# ST-LINK.net
KiCad netlist of a schematic drawn in Altium Designer
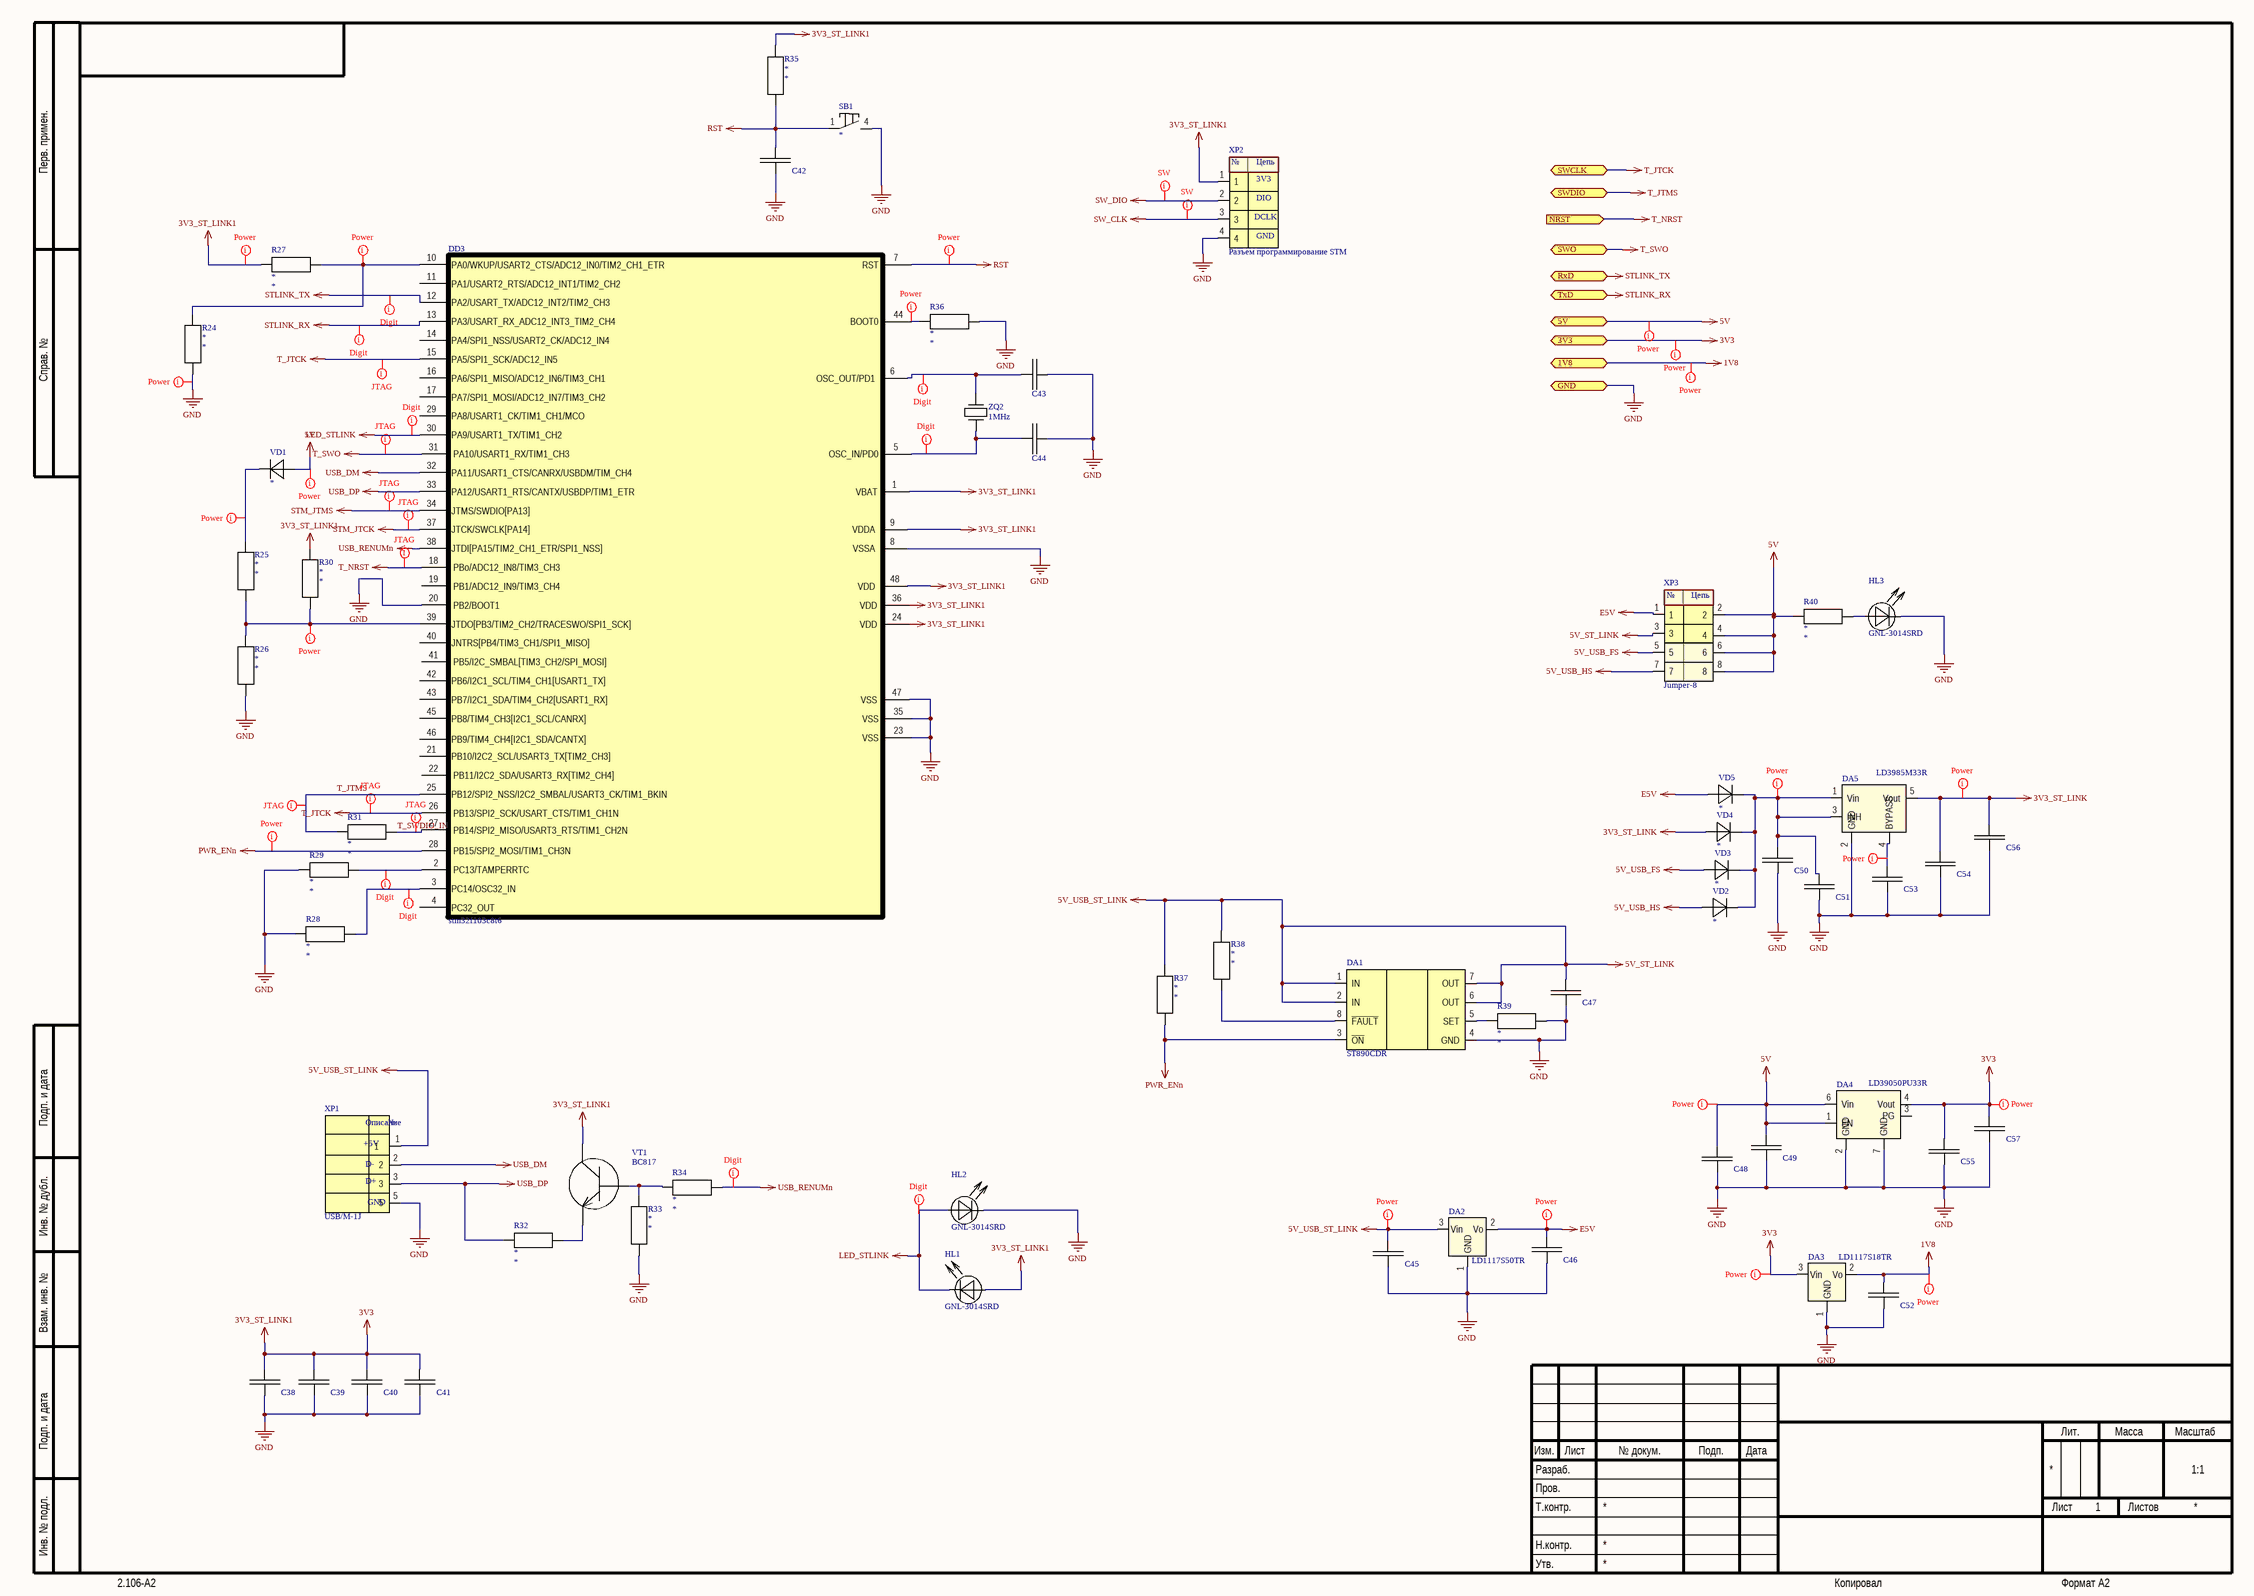
[diagram p0: ST-LINK.SchDoc]

(export (version "E")
  (design (tool "Eeschema 10.0.6"))
  (components
    (comp (ref "C38") (value "*") (footprint "CAP0402") (libsource (lib "SchlibUGO") (part "Capasitor")))
    (comp (ref "C39") (value "*") (footprint "CAP0402") (libsource (lib "SchlibUGO") (part "Capasitor")))
    (comp (ref "C40") (value "*") (footprint "CAP0402") (libsource (lib "SchlibUGO") (part "Capasitor")))
    (comp (ref "C41") (value "*") (footprint "CAP0402") (libsource (lib "SchlibUGO") (part "Capasitor")))
    (comp (ref "C42") (value "*") (footprint "CAP0402") (libsource (lib "SchlibUGO") (part "Capasitor")))
    (comp (ref "C43") (value "*") (footprint "CAP0402") (libsource (lib "SchlibUGO") (part "Capasitor")))
    (comp (ref "C44") (value "*") (footprint "CAP0402") (libsource (lib "SchlibUGO") (part "Capasitor")))
    (comp (ref "C45") (value "*") (footprint "CAP0402") (libsource (lib "SchlibUGO") (part "Capasitor")))
    (comp (ref "C46") (value "*") (footprint "CAP0402") (libsource (lib "SchlibUGO") (part "Capasitor")))
    (comp (ref "C47") (value "*") (footprint "CAP0402") (libsource (lib "SchlibUGO") (part "Capasitor")))
    (comp (ref "C48") (value "*") (footprint "CAP0402") (libsource (lib "SchlibUGO") (part "Capasitor")))
    (comp (ref "C49") (value "*") (footprint "CAP0402") (libsource (lib "SchlibUGO") (part "Capasitor")))
    (comp (ref "C50") (value "*") (footprint "CAP0402") (libsource (lib "SchlibUGO") (part "Capasitor")))
    (comp (ref "C51") (value "*") (footprint "CAP0402") (libsource (lib "SchlibUGO") (part "Capasitor")))
    (comp (ref "C52") (value "*") (footprint "CAP0402") (libsource (lib "SchlibUGO") (part "Capasitor")))
    (comp (ref "C53") (value "*") (footprint "CAP0402") (libsource (lib "SchlibUGO") (part "Capasitor")))
    (comp (ref "C54") (value "*") (footprint "CAP0402") (libsource (lib "SchlibUGO") (part "Capasitor")))
    (comp (ref "C55") (value "*") (footprint "CAP0402") (libsource (lib "SchlibUGO") (part "Capasitor")))
    (comp (ref "C56") (value "*") (footprint "CAP0402") (libsource (lib "SchlibUGO") (part "Capasitor")))
    (comp (ref "C57") (value "*") (footprint "CAP0402") (libsource (lib "SchlibUGO") (part "Capasitor")))
    (comp (ref "DA1")
      (value "ST890CDR")
      (footprint "SO-8")
      (fields (field (name "MANUFACTURER") "Texas Instruments"))
      (libsource (lib "SchlibUGO") (part "ST890CDR"))
    )
    (comp (ref "DA2")
      (value "LD1117S50TR")
      (footprint "SOD-223")
      (fields (field (name "MANUFACTURER") "Texas Instruments"))
      (libsource (lib "SchlibUGO") (part "LD1117S50TR"))
    )
    (comp (ref "DA3")
      (value "LD1117S18TR")
      (footprint "SOD-223")
      (fields (field (name "MANUFACTURER") "Texas Instruments"))
      (libsource (lib "SchlibUGO") (part "LD1117S18TR"))
    )
    (comp (ref "DA4")
      (value "LD39050PU33R")
      (footprint "DFN-6(3x3)")
      (fields (field (name "MANUFACTURER") "Texas Instruments"))
      (libsource (lib "SchlibUGO") (part "LD39050PU33R"))
    )
    (comp (ref "DA5")
      (value "LD3985M33R")
      (footprint "SOT23-5")
      (fields (field (name "MANUFACTURER") "Texas Instruments"))
      (libsource (lib "SchlibUGO") (part "LD3985M33R"))
    )
    (comp (ref "DD3")
      (value "stm32f103c8t6")
      (footprint "LQFP48")
      (fields (field (name "MANUFACTURER") "STM"))
      (libsource (lib "SchlibUGO") (part "stm32f103c8t6"))
    )
    (comp (ref "HL1")
      (value "GNL-3014SRD")
      (footprint "LED1206")
      (fields (field (name "MANUFACTURER") "G-NOR"))
      (libsource (lib "") (part "LED_1"))
    )
    (comp (ref "HL2")
      (value "GNL-3014SRD")
      (footprint "LED1206")
      (fields (field (name "MANUFACTURER") "G-NOR"))
      (libsource (lib "SchlibUGO") (part "LED"))
    )
    (comp (ref "HL3")
      (value "GNL-3014SRD")
      (footprint "LED1206")
      (fields (field (name "MANUFACTURER") "G-NOR"))
      (libsource (lib "SchlibUGO") (part "LED"))
    )
    (comp (ref "R24")
      (value "*")
      (footprint "0402")
      (fields (field (name "ALTIUM_VALUE") "*") (field (name "POWER") "*"))
      (libsource (lib "SchlibUGO") (part "Resistor"))
    )
    (comp (ref "R25")
      (value "*")
      (footprint "0402")
      (fields (field (name "ALTIUM_VALUE") "*") (field (name "POWER") "*"))
      (libsource (lib "SchlibUGO") (part "Resistor"))
    )
    (comp (ref "R26")
      (value "*")
      (footprint "0402")
      (fields (field (name "ALTIUM_VALUE") "*") (field (name "POWER") "*"))
      (libsource (lib "SchlibUGO") (part "Resistor"))
    )
    (comp (ref "R27")
      (value "*")
      (footprint "0402")
      (fields (field (name "ALTIUM_VALUE") "*") (field (name "POWER") "*"))
      (libsource (lib "SchlibUGO") (part "Resistor"))
    )
    (comp (ref "R28")
      (value "*")
      (footprint "0402")
      (fields (field (name "ALTIUM_VALUE") "*") (field (name "POWER") "*"))
      (libsource (lib "SchlibUGO") (part "Resistor"))
    )
    (comp (ref "R29")
      (value "*")
      (footprint "0402")
      (fields (field (name "ALTIUM_VALUE") "*") (field (name "POWER") "*"))
      (libsource (lib "SchlibUGO") (part "Resistor"))
    )
    (comp (ref "R30")
      (value "*")
      (footprint "0402")
      (fields (field (name "ALTIUM_VALUE") "*") (field (name "POWER") "*"))
      (libsource (lib "SchlibUGO") (part "Resistor"))
    )
    (comp (ref "R31")
      (value "*")
      (footprint "0402")
      (fields (field (name "ALTIUM_VALUE") "*") (field (name "POWER") "*"))
      (libsource (lib "SchlibUGO") (part "Resistor"))
    )
    (comp (ref "R32")
      (value "*")
      (footprint "0402")
      (fields (field (name "ALTIUM_VALUE") "*") (field (name "POWER") "*"))
      (libsource (lib "SchlibUGO") (part "Resistor"))
    )
    (comp (ref "R33")
      (value "*")
      (footprint "0402")
      (fields (field (name "ALTIUM_VALUE") "*") (field (name "POWER") "*"))
      (libsource (lib "SchlibUGO") (part "Resistor"))
    )
    (comp (ref "R34")
      (value "*")
      (footprint "0402")
      (fields (field (name "ALTIUM_VALUE") "*") (field (name "POWER") "*"))
      (libsource (lib "SchlibUGO") (part "Resistor"))
    )
    (comp (ref "R35")
      (value "*")
      (footprint "0402")
      (fields (field (name "ALTIUM_VALUE") "*") (field (name "POWER") "*"))
      (libsource (lib "SchlibUGO") (part "Resistor"))
    )
    (comp (ref "R36")
      (value "*")
      (footprint "0402")
      (fields (field (name "ALTIUM_VALUE") "*") (field (name "POWER") "*"))
      (libsource (lib "SchlibUGO") (part "Resistor"))
    )
    (comp (ref "R37")
      (value "*")
      (footprint "0402")
      (fields (field (name "ALTIUM_VALUE") "*") (field (name "POWER") "*"))
      (libsource (lib "SchlibUGO") (part "Resistor"))
    )
    (comp (ref "R38")
      (value "*")
      (footprint "0402")
      (fields (field (name "ALTIUM_VALUE") "*") (field (name "POWER") "*"))
      (libsource (lib "SchlibUGO") (part "Resistor"))
    )
    (comp (ref "R39")
      (value "*")
      (footprint "0402")
      (fields (field (name "ALTIUM_VALUE") "*") (field (name "POWER") "*"))
      (libsource (lib "SchlibUGO") (part "Resistor"))
    )
    (comp (ref "R40")
      (value "*")
      (footprint "0402")
      (fields (field (name "ALTIUM_VALUE") "*") (field (name "POWER") "*"))
      (libsource (lib "SchlibUGO") (part "Resistor"))
    )
    (comp (ref "SB1") (value "*") (footprint "KLS2") (libsource (lib "SchlibUGO") (part "Button")))
    (comp (ref "VD1") (value "*") (footprint "melf") (libsource (lib "Diode_Library") (part "Basic_Diode")))
    (comp (ref "VD2")
      (value "*")
      (footprint "MINIMELF")
      (libsource (lib "Diode_Library") (part "Basic_Diode"))
    )
    (comp (ref "VD3")
      (value "*")
      (footprint "MINIMELF")
      (libsource (lib "Diode_Library") (part "Basic_Diode"))
    )
    (comp (ref "VD4")
      (value "*")
      (footprint "MINIMELF")
      (libsource (lib "Diode_Library") (part "Basic_Diode"))
    )
    (comp (ref "VD5")
      (value "*")
      (footprint "MINIMELF")
      (libsource (lib "Diode_Library") (part "Basic_Diode"))
    )
    (comp (ref "VT1")
      (value "BC817")
      (footprint "SOT23-3")
      (fields (field (name "MANUFACTURER") "NXP Semiconductors"))
      (libsource (lib "Project_int_VT") (part "BC817"))
    )
    (comp (ref "XP1")
      (value "USB/M-1J")
      (footprint "USB/M-1J")
      (fields (field (name "MANUFACTURER") "ESB"))
      (libsource (lib "SchlibUGO") (part "USB-M-1J"))
    )
    (comp (ref "XP2")
      (value "Разъем программирование STM")
      (footprint "Connector_STKLink")
      (libsource (lib "SchlibUGO") (part "Connector_STKLink"))
    )
    (comp (ref "XP3")
      (value "Jumper-8")
      (footprint "PLS-4-2")
      (libsource (lib "SchlibUGO") (part "Jumper-8"))
    )
    (comp (ref "ZQ2")
      (value "1MHz")
      (footprint "HC-51U")
      (fields (field (name "PART NUMBER") "HC-51") (field (name "MANUFACTURER") "CHina"))
      (libsource (lib "SchlibUGO") (part "Rzanator"))
    )
  )
  (nets
    (net (code "1") (name "/T_SWDIO_IN") (class "Default")
      (node (ref "DD3") (pin "27") (pinfunction "PB14/SPI2_MISO/USART3_RTS/TIM1_CH2N_27") (pintype "passive"))
      (node (ref "R31") (pin "2") (pinfunction "2_2") (pintype "passive"))
    )
    (net (code "2") (name "1V8") (class "Default")
      (node (ref "C52") (pin "1") (pinfunction "1_1") (pintype "passive"))
      (node (ref "DA3") (pin "2") (pinfunction "Vo_2") (pintype "passive"))
    )
    (net (code "3") (name "3V3") (class "Default")
      (node (ref "C38") (pin "1") (pinfunction "1_1") (pintype "passive"))
      (node (ref "C39") (pin "1") (pinfunction "1_1") (pintype "passive"))
      (node (ref "C40") (pin "1") (pinfunction "1_1") (pintype "passive"))
      (node (ref "C41") (pin "1") (pinfunction "1_1") (pintype "passive"))
      (node (ref "C55") (pin "1") (pinfunction "1_1") (pintype "passive"))
      (node (ref "C57") (pin "1") (pinfunction "1_1") (pintype "passive"))
      (node (ref "DA3") (pin "3") (pinfunction "Vin_3") (pintype "passive"))
      (node (ref "DA4") (pin "4") (pinfunction "Vout_4") (pintype "passive"))
      (node (ref "DD3") (pin "1") (pinfunction "VBAT_1") (pintype "passive"))
      (node (ref "DD3") (pin "24") (pinfunction "VDD_24") (pintype "passive"))
      (node (ref "DD3") (pin "36") (pinfunction "VDD_36") (pintype "passive"))
      (node (ref "DD3") (pin "48") (pinfunction "VDD_48") (pintype "passive"))
      (node (ref "DD3") (pin "9") (pinfunction "VDDA_9") (pintype "passive"))
      (node (ref "HL1") (pin "1") (pinfunction "1_1") (pintype "passive"))
      (node (ref "R27") (pin "1") (pinfunction "1_1") (pintype "passive"))
      (node (ref "R30") (pin "2") (pinfunction "2_2") (pintype "passive"))
      (node (ref "R35") (pin "2") (pinfunction "2_2") (pintype "passive"))
      (node (ref "VT1") (pin "3") (pinfunction "3_3") (pintype "passive"))
      (node (ref "XP2") (pin "1") (pinfunction "1_1") (pintype "passive"))
    )
    (net (code "4") (name "3V3_ST_LINK") (class "Default")
      (node (ref "C54") (pin "1") (pinfunction "1_1") (pintype "passive"))
      (node (ref "C56") (pin "1") (pinfunction "1_1") (pintype "passive"))
      (node (ref "DA5") (pin "5") (pinfunction "Vout_5") (pintype "passive"))
      (node (ref "VD4") (pin "1") (pinfunction "1_1") (pintype "passive"))
    )
    (net (code "5") (name "5V") (class "Default")
      (node (ref "C48") (pin "1") (pinfunction "1_1") (pintype "passive"))
      (node (ref "C49") (pin "1") (pinfunction "1_1") (pintype "passive"))
      (node (ref "DA4") (pin "1") (pinfunction "EN_1") (pintype "passive"))
      (node (ref "DA4") (pin "6") (pinfunction "Vin_6") (pintype "passive"))
      (node (ref "R40") (pin "2") (pinfunction "2_2") (pintype "passive"))
      (node (ref "VD1") (pin "1") (pinfunction "1_1") (pintype "passive"))
      (node (ref "XP3") (pin "2") (pinfunction "2_2") (pintype "passive"))
      (node (ref "XP3") (pin "4") (pinfunction "4_4") (pintype "passive"))
      (node (ref "XP3") (pin "6") (pinfunction "6_6") (pintype "passive"))
      (node (ref "XP3") (pin "8") (pinfunction "8_8") (pintype "passive"))
    )
    (net (code "6") (name "5V_ST_LINK") (class "Default")
      (node (ref "C45") (pin "1") (pinfunction "1_1") (pintype "passive"))
      (node (ref "C47") (pin "1") (pinfunction "1_1") (pintype "passive"))
      (node (ref "DA1") (pin "1") (pinfunction "IN_1") (pintype "passive"))
      (node (ref "DA1") (pin "2") (pinfunction "IN_2") (pintype "passive"))
      (node (ref "DA1") (pin "6") (pinfunction "OUT_6") (pintype "passive"))
      (node (ref "DA1") (pin "7") (pinfunction "OUT_7") (pintype "passive"))
      (node (ref "DA2") (pin "3") (pinfunction "Vin_3") (pintype "passive"))
      (node (ref "R37") (pin "2") (pinfunction "2_2") (pintype "passive"))
      (node (ref "R38") (pin "2") (pinfunction "2_2") (pintype "passive"))
      (node (ref "XP1") (pin "1") (pinfunction "1_1") (pintype "passive"))
      (node (ref "XP3") (pin "3") (pinfunction "3_3") (pintype "passive"))
    )
    (net (code "7") (name "5V_USB_FS") (class "Default")
      (node (ref "VD3") (pin "1") (pinfunction "1_1") (pintype "passive"))
      (node (ref "XP3") (pin "5") (pinfunction "5_5") (pintype "passive"))
    )
    (net (code "8") (name "5V_USB_HS") (class "Default")
      (node (ref "VD2") (pin "1") (pinfunction "1_1") (pintype "passive"))
      (node (ref "XP3") (pin "7") (pinfunction "7_7") (pintype "passive"))
    )
    (net (code "9") (name "E5V") (class "Default")
      (node (ref "C46") (pin "1") (pinfunction "1_1") (pintype "passive"))
      (node (ref "DA2") (pin "2") (pinfunction "Vo_2") (pintype "passive"))
      (node (ref "VD5") (pin "1") (pinfunction "1_1") (pintype "passive"))
      (node (ref "XP3") (pin "1") (pinfunction "1_1") (pintype "passive"))
    )
    (net (code "10") (name "GND") (class "Default")
      (node (ref "C38") (pin "2") (pinfunction "2_2") (pintype "passive"))
      (node (ref "C39") (pin "2") (pinfunction "2_2") (pintype "passive"))
      (node (ref "C40") (pin "2") (pinfunction "2_2") (pintype "passive"))
      (node (ref "C41") (pin "2") (pinfunction "2_2") (pintype "passive"))
      (node (ref "C42") (pin "2") (pinfunction "2_2") (pintype "passive"))
      (node (ref "C43") (pin "2") (pinfunction "2_2") (pintype "passive"))
      (node (ref "C44") (pin "2") (pinfunction "2_2") (pintype "passive"))
      (node (ref "C45") (pin "2") (pinfunction "2_2") (pintype "passive"))
      (node (ref "C46") (pin "2") (pinfunction "2_2") (pintype "passive"))
      (node (ref "C47") (pin "2") (pinfunction "2_2") (pintype "passive"))
      (node (ref "C48") (pin "2") (pinfunction "2_2") (pintype "passive"))
      (node (ref "C49") (pin "2") (pinfunction "2_2") (pintype "passive"))
      (node (ref "C50") (pin "2") (pinfunction "2_2") (pintype "passive"))
      (node (ref "C51") (pin "2") (pinfunction "2_2") (pintype "passive"))
      (node (ref "C52") (pin "2") (pinfunction "2_2") (pintype "passive"))
      (node (ref "C53") (pin "2") (pinfunction "2_2") (pintype "passive"))
      (node (ref "C54") (pin "2") (pinfunction "2_2") (pintype "passive"))
      (node (ref "C55") (pin "2") (pinfunction "2_2") (pintype "passive"))
      (node (ref "C56") (pin "2") (pinfunction "2_2") (pintype "passive"))
      (node (ref "C57") (pin "2") (pinfunction "2_2") (pintype "passive"))
      (node (ref "DA1") (pin "4") (pinfunction "GND_4") (pintype "passive"))
      (node (ref "DA2") (pin "1") (pinfunction "GND_1") (pintype "passive"))
      (node (ref "DA3") (pin "1") (pinfunction "GND_1") (pintype "passive"))
      (node (ref "DA4") (pin "2") (pinfunction "GND_2") (pintype "passive"))
      (node (ref "DA4") (pin "7") (pinfunction "GND_7") (pintype "passive"))
      (node (ref "DA5") (pin "2") (pinfunction "GND_2") (pintype "passive"))
      (node (ref "DD3") (pin "20") (pinfunction "PB2/BOOT1_20") (pintype "passive"))
      (node (ref "DD3") (pin "23") (pinfunction "VSS_23") (pintype "passive"))
      (node (ref "DD3") (pin "35") (pinfunction "VSS_35") (pintype "passive"))
      (node (ref "DD3") (pin "47") (pinfunction "VSS_47") (pintype "passive"))
      (node (ref "DD3") (pin "8") (pinfunction "VSSA_8") (pintype "passive"))
      (node (ref "HL2") (pin "2") (pinfunction "2_2") (pintype "passive"))
      (node (ref "HL3") (pin "2") (pinfunction "2_2") (pintype "passive"))
      (node (ref "R24") (pin "1") (pinfunction "1_1") (pintype "passive"))
      (node (ref "R26") (pin "1") (pinfunction "1_1") (pintype "passive"))
      (node (ref "R28") (pin "1") (pinfunction "1_1") (pintype "passive"))
      (node (ref "R29") (pin "1") (pinfunction "1_1") (pintype "passive"))
      (node (ref "R33") (pin "1") (pinfunction "1_1") (pintype "passive"))
      (node (ref "R36") (pin "1") (pinfunction "1_1") (pintype "passive"))
      (node (ref "R39") (pin "1") (pinfunction "1_1") (pintype "passive"))
      (node (ref "SB1") (pin "4") (pinfunction "4_4") (pintype "passive"))
      (node (ref "XP1") (pin "5") (pinfunction "5_5") (pintype "passive"))
      (node (ref "XP2") (pin "4") (pinfunction "4_4") (pintype "passive"))
    )
    (net (code "11") (name "LED_STLINK") (class "Default")
      (node (ref "DD3") (pin "30") (pinfunction "PA9/USART1_TX/TIM1_CH2_30") (pintype "passive"))
      (node (ref "HL1") (pin "2") (pinfunction "2_2") (pintype "passive"))
      (node (ref "HL2") (pin "1") (pinfunction "1_1") (pintype "passive"))
    )
    (net (code "12") (name "Net-(DA1-SET)") (class "Default")
      (node (ref "DA1") (pin "5") (pinfunction "SET_5") (pintype "passive"))
      (node (ref "R39") (pin "2") (pinfunction "2_2") (pintype "passive"))
    )
    (net (code "13") (name "Net-(DA1-~{FAULT})") (class "Default")
      (node (ref "DA1") (pin "8") (pinfunction "~{FAULT}_8") (pintype "passive"))
      (node (ref "R38") (pin "1") (pinfunction "1_1") (pintype "passive"))
    )
    (net (code "14") (name "Net-(DA5-BYPASS)") (class "Default")
      (node (ref "C53") (pin "1") (pinfunction "1_1") (pintype "passive"))
      (node (ref "DA5") (pin "4") (pinfunction "BYPASS_4") (pintype "passive"))
    )
    (net (code "15") (name "Net-(DA5-INH)") (class "Default")
      (node (ref "C50") (pin "1") (pinfunction "1_1") (pintype "passive"))
      (node (ref "C51") (pin "1") (pinfunction "1_1") (pintype "passive"))
      (node (ref "DA5") (pin "1") (pinfunction "Vin_1") (pintype "passive"))
      (node (ref "DA5") (pin "3") (pinfunction "INH_3") (pintype "passive"))
      (node (ref "VD2") (pin "2") (pinfunction "2_2") (pintype "passive"))
      (node (ref "VD3") (pin "2") (pinfunction "2_2") (pintype "passive"))
      (node (ref "VD4") (pin "2") (pinfunction "2_2") (pintype "passive"))
      (node (ref "VD5") (pin "2") (pinfunction "2_2") (pintype "passive"))
    )
    (net (code "16") (name "Net-(DD3-BOOT0)") (class "Default")
      (node (ref "DD3") (pin "44") (pinfunction "BOOT0_44") (pintype "passive"))
      (node (ref "R36") (pin "2") (pinfunction "2_2") (pintype "passive"))
    )
    (net (code "17") (name "Net-(DD3-JTDO[PB3{slash}TIM2_CH2{slash}TRACESWO{slash}SPI1_SCK])") (class "Default")
      (node (ref "DD3") (pin "39") (pinfunction "JTDO[PB3/TIM2_CH2/TRACESWO/SPI1_SCK]_39") (pintype "passive"))
      (node (ref "R25") (pin "1") (pinfunction "1_1") (pintype "passive"))
      (node (ref "R26") (pin "2") (pinfunction "2_2") (pintype "passive"))
      (node (ref "R30") (pin "1") (pinfunction "1_1") (pintype "passive"))
    )
    (net (code "18") (name "Net-(DD3-OSC_IN{slash}PD0)") (class "Default")
      (node (ref "C44") (pin "1") (pinfunction "1_1") (pintype "passive"))
      (node (ref "DD3") (pin "5") (pinfunction "OSC_IN/PD0_5") (pintype "passive"))
      (node (ref "ZQ2") (pin "1") (pinfunction "1_1") (pintype "passive"))
    )
    (net (code "19") (name "Net-(DD3-OSC_OUT{slash}PD1)") (class "Default")
      (node (ref "C43") (pin "1") (pinfunction "1_1") (pintype "passive"))
      (node (ref "DD3") (pin "6") (pinfunction "OSC_OUT/PD1_6") (pintype "passive"))
      (node (ref "ZQ2") (pin "3") (pinfunction "2_3") (pintype "passive"))
    )
    (net (code "20") (name "Net-(DD3-PA0{slash}WKUP{slash}USART2_CTS{slash}ADC12_IN0{slash}TIM2_CH1_ETR)") (class "Default")
      (node (ref "DD3") (pin "10") (pinfunction "PA0/WKUP/USART2_CTS/ADC12_IN0/TIM2_CH1_ETR_10") (pintype "passive"))
      (node (ref "R24") (pin "2") (pinfunction "2_2") (pintype "passive"))
      (node (ref "R27") (pin "2") (pinfunction "2_2") (pintype "passive"))
    )
    (net (code "21") (name "Net-(DD3-PC13{slash}TAMPERRTC)") (class "Default")
      (node (ref "DD3") (pin "2") (pinfunction "PC13/TAMPERRTC_2") (pintype "passive"))
      (node (ref "R29") (pin "2") (pinfunction "2_2") (pintype "passive"))
    )
    (net (code "22") (name "Net-(DD3-PC14{slash}OSC32_IN)") (class "Default")
      (node (ref "DD3") (pin "3") (pinfunction "PC14/OSC32_IN_3") (pintype "passive"))
      (node (ref "R28") (pin "2") (pinfunction "2_2") (pintype "passive"))
    )
    (net (code "23") (name "Net-(HL3-Pad1)") (class "Default")
      (node (ref "HL3") (pin "1") (pinfunction "1_1") (pintype "passive"))
      (node (ref "R40") (pin "1") (pinfunction "1_1") (pintype "passive"))
    )
    (net (code "24") (name "Net-(R25-Pad2)") (class "Default")
      (node (ref "R25") (pin "2") (pinfunction "2_2") (pintype "passive"))
      (node (ref "VD1") (pin "2") (pinfunction "2_2") (pintype "passive"))
    )
    (net (code "25") (name "Net-(R32-Pad2)") (class "Default")
      (node (ref "R32") (pin "2") (pinfunction "2_2") (pintype "passive"))
      (node (ref "VT1") (pin "2") (pinfunction "2_2") (pintype "passive"))
    )
    (net (code "26") (name "Net-(R33-Pad2)") (class "Default")
      (node (ref "R33") (pin "2") (pinfunction "2_2") (pintype "passive"))
      (node (ref "R34") (pin "1") (pinfunction "1_1") (pintype "passive"))
      (node (ref "VT1") (pin "1") (pinfunction "1_1") (pintype "passive"))
    )
    (net (code "27") (name "PWR_ENn") (class "Default")
      (node (ref "DA1") (pin "3") (pinfunction "~{ON}_3") (pintype "passive"))
      (node (ref "DD3") (pin "28") (pinfunction "PB15/SPI2_MOSI/TIM1_CH3N_28") (pintype "passive"))
      (node (ref "R37") (pin "1") (pinfunction "1_1") (pintype "passive"))
    )
    (net (code "28") (name "RST") (class "Default")
      (node (ref "C42") (pin "1") (pinfunction "1_1") (pintype "passive"))
      (node (ref "DD3") (pin "7") (pinfunction "RST_7") (pintype "passive"))
      (node (ref "R35") (pin "1") (pinfunction "1_1") (pintype "passive"))
      (node (ref "SB1") (pin "1") (pinfunction "1_1") (pintype "passive"))
    )
    (net (code "29") (name "STLINK_RX") (class "Default")
      (node (ref "DD3") (pin "13") (pinfunction "PA3/USART_RX_ADC12_INT3_TIM2_CH4_13") (pintype "passive"))
    )
    (net (code "30") (name "STLINK_TX") (class "Default")
      (node (ref "DD3") (pin "12") (pinfunction "PA2/USART_TX/ADC12_INT2/TIM2_CH3_12") (pintype "passive"))
    )
    (net (code "31") (name "STM_JTCK") (class "Default")
      (node (ref "DD3") (pin "37") (pinfunction "JTCK/SWCLK[PA14]_37") (pintype "passive"))
    )
    (net (code "32") (name "STM_JTMS") (class "Default")
      (node (ref "DD3") (pin "34") (pinfunction "JTMS/SWDIO[PA13]_34") (pintype "passive"))
    )
    (net (code "33") (name "SW_CLK") (class "Default")
      (node (ref "XP2") (pin "3") (pinfunction "3_3") (pintype "passive"))
    )
    (net (code "34") (name "SW_DIO") (class "Default")
      (node (ref "XP2") (pin "2") (pinfunction "2_2") (pintype "passive"))
    )
    (net (code "35") (name "T_JTCK") (class "Default")
      (node (ref "DD3") (pin "15") (pinfunction "PA5/SPI1_SCK/ADC12_IN5_15") (pintype "passive"))
      (node (ref "DD3") (pin "26") (pinfunction "PB13/SPI2_SCK/USART_CTS/TIM1_CH1N_26") (pintype "passive"))
    )
    (net (code "36") (name "T_JTMS") (class "Default")
      (node (ref "DD3") (pin "25") (pinfunction "PB12/SPI2_NSS/I2C2_SMBAL/USART3_CK/TIM1_BKIN_25") (pintype "passive"))
      (node (ref "R31") (pin "1") (pinfunction "1_1") (pintype "passive"))
    )
    (net (code "37") (name "T_NRST") (class "Default")
      (node (ref "DD3") (pin "18") (pinfunction "PBo/ADC12_IN8/TIM3_CH3_18") (pintype "passive"))
    )
    (net (code "38") (name "T_SWO") (class "Default")
      (node (ref "DD3") (pin "31") (pinfunction "PA10/USART1_RX/TIM1_CH3_31") (pintype "passive"))
    )
    (net (code "39") (name "USB_DM") (class "Default")
      (node (ref "DD3") (pin "32") (pinfunction "PA11/USART1_CTS/CANRX/USBDM/TIM_CH4_32") (pintype "passive"))
      (node (ref "XP1") (pin "2") (pinfunction "2_2") (pintype "passive"))
    )
    (net (code "40") (name "USB_DP") (class "Default")
      (node (ref "DD3") (pin "33") (pinfunction "PA12/USART1_RTS/CANTX/USBDP/TIM1_ETR_33") (pintype "passive"))
      (node (ref "R32") (pin "1") (pinfunction "1_1") (pintype "passive"))
      (node (ref "XP1") (pin "3") (pinfunction "3_3") (pintype "passive"))
    )
    (net (code "41") (name "USB_RENUMn") (class "Default")
      (node (ref "DD3") (pin "38") (pinfunction "JTDI[PA15/TIM2_CH1_ETR/SPI1_NSS]_38") (pintype "passive"))
      (node (ref "R34") (pin "2") (pinfunction "2_2") (pintype "passive"))
    )
    (net (code "42") (name "unconnected-(DA4-PG-Pad3)") (class "Default")
      (node (ref "DA4") (pin "3") (pinfunction "PG_3") (pintype "passive"))
    )
    (net (code "43") (name "unconnected-(DD3-JNTRS[PB4{slash}TIM3_CH1{slash}SPI1_MISO]-Pad40)") (class "Default")
      (node (ref "DD3") (pin "40") (pinfunction "JNTRS[PB4/TIM3_CH1/SPI1_MISO]_40") (pintype "passive"))
    )
    (net (code "44") (name "unconnected-(DD3-PA1{slash}USART2_RTS{slash}ADC12_INT1{slash}TIM2_CH2-Pad11)") (class "Default")
      (node (ref "DD3") (pin "11") (pinfunction "PA1/USART2_RTS/ADC12_INT1/TIM2_CH2_11") (pintype "passive"))
    )
    (net (code "45") (name "unconnected-(DD3-PA4{slash}SPI1_NSS{slash}USART2_CK{slash}ADC12_IN4-Pad14)") (class "Default")
      (node (ref "DD3") (pin "14") (pinfunction "PA4/SPI1_NSS/USART2_CK/ADC12_IN4_14") (pintype "passive"))
    )
    (net (code "46") (name "unconnected-(DD3-PA6{slash}SPI1_MISO{slash}ADC12_IN6{slash}TIM3_CH1-Pad16)") (class "Default")
      (node (ref "DD3") (pin "16") (pinfunction "PA6/SPI1_MISO/ADC12_IN6/TIM3_CH1_16") (pintype "passive"))
    )
    (net (code "47") (name "unconnected-(DD3-PA7{slash}SPI1_MOSI{slash}ADC12_IN7{slash}TIM3_CH2-Pad17)") (class "Default")
      (node (ref "DD3") (pin "17") (pinfunction "PA7/SPI1_MOSI/ADC12_IN7/TIM3_CH2_17") (pintype "passive"))
    )
    (net (code "48") (name "unconnected-(DD3-PA8{slash}USART1_CK{slash}TIM1_CH1{slash}MCO-Pad29)") (class "Default")
      (node (ref "DD3") (pin "29") (pinfunction "PA8/USART1_CK/TIM1_CH1/MCO_29") (pintype "passive"))
    )
    (net (code "49") (name "unconnected-(DD3-PB1{slash}ADC12_IN9{slash}TIM3_CH4-Pad19)") (class "Default")
      (node (ref "DD3") (pin "19") (pinfunction "PB1/ADC12_IN9/TIM3_CH4_19") (pintype "passive"))
    )
    (net (code "50") (name "unconnected-(DD3-PB5{slash}I2C_SMBAL[TIM3_CH2{slash}SPI_MOSI]-Pad41)") (class "Default")
      (node (ref "DD3") (pin "41") (pinfunction "PB5/I2C_SMBAL[TIM3_CH2/SPI_MOSI]_41") (pintype "passive"))
    )
    (net (code "51") (name "unconnected-(DD3-PB6{slash}I2C1_SCL{slash}TIM4_CH1[USART1_TX]-Pad42)") (class "Default")
      (node (ref "DD3") (pin "42") (pinfunction "PB6/I2C1_SCL/TIM4_CH1[USART1_TX]_42") (pintype "passive"))
    )
    (net (code "52") (name "unconnected-(DD3-PB7{slash}I2C1_SDA{slash}TIM4_CH2[USART1_RX]-Pad43)") (class "Default")
      (node (ref "DD3") (pin "43") (pinfunction "PB7/I2C1_SDA/TIM4_CH2[USART1_RX]_43") (pintype "passive"))
    )
    (net (code "53") (name "unconnected-(DD3-PB8{slash}TIM4_CH3[I2C1_SCL{slash}CANRX]-Pad45)") (class "Default")
      (node (ref "DD3") (pin "45") (pinfunction "PB8/TIM4_CH3[I2C1_SCL/CANRX]_45") (pintype "passive"))
    )
    (net (code "54") (name "unconnected-(DD3-PB9{slash}TIM4_CH4[I2C1_SDA{slash}CANTX]-Pad46)") (class "Default")
      (node (ref "DD3") (pin "46") (pinfunction "PB9/TIM4_CH4[I2C1_SDA/CANTX]_46") (pintype "passive"))
    )
    (net (code "55") (name "unconnected-(DD3-PB10{slash}I2C2_SCL{slash}USART3_TX[TIM2_CH3]-Pad21)") (class "Default")
      (node (ref "DD3") (pin "21") (pinfunction "PB10/I2C2_SCL/USART3_TX[TIM2_CH3]_21") (pintype "passive"))
    )
    (net (code "56") (name "unconnected-(DD3-PB11{slash}I2C2_SDA{slash}USART3_RX[TIM2_CH4]-Pad22)") (class "Default")
      (node (ref "DD3") (pin "22") (pinfunction "PB11/I2C2_SDA/USART3_RX[TIM2_CH4]_22") (pintype "passive"))
    )
    (net (code "57") (name "unconnected-(DD3-PC32_OUT-Pad4)") (class "Default")
      (node (ref "DD3") (pin "4") (pinfunction "PC32_OUT_4") (pintype "passive"))
    )
  )
)
